# tester.net
KiCad netlist of a schematic drawn in EAGLE
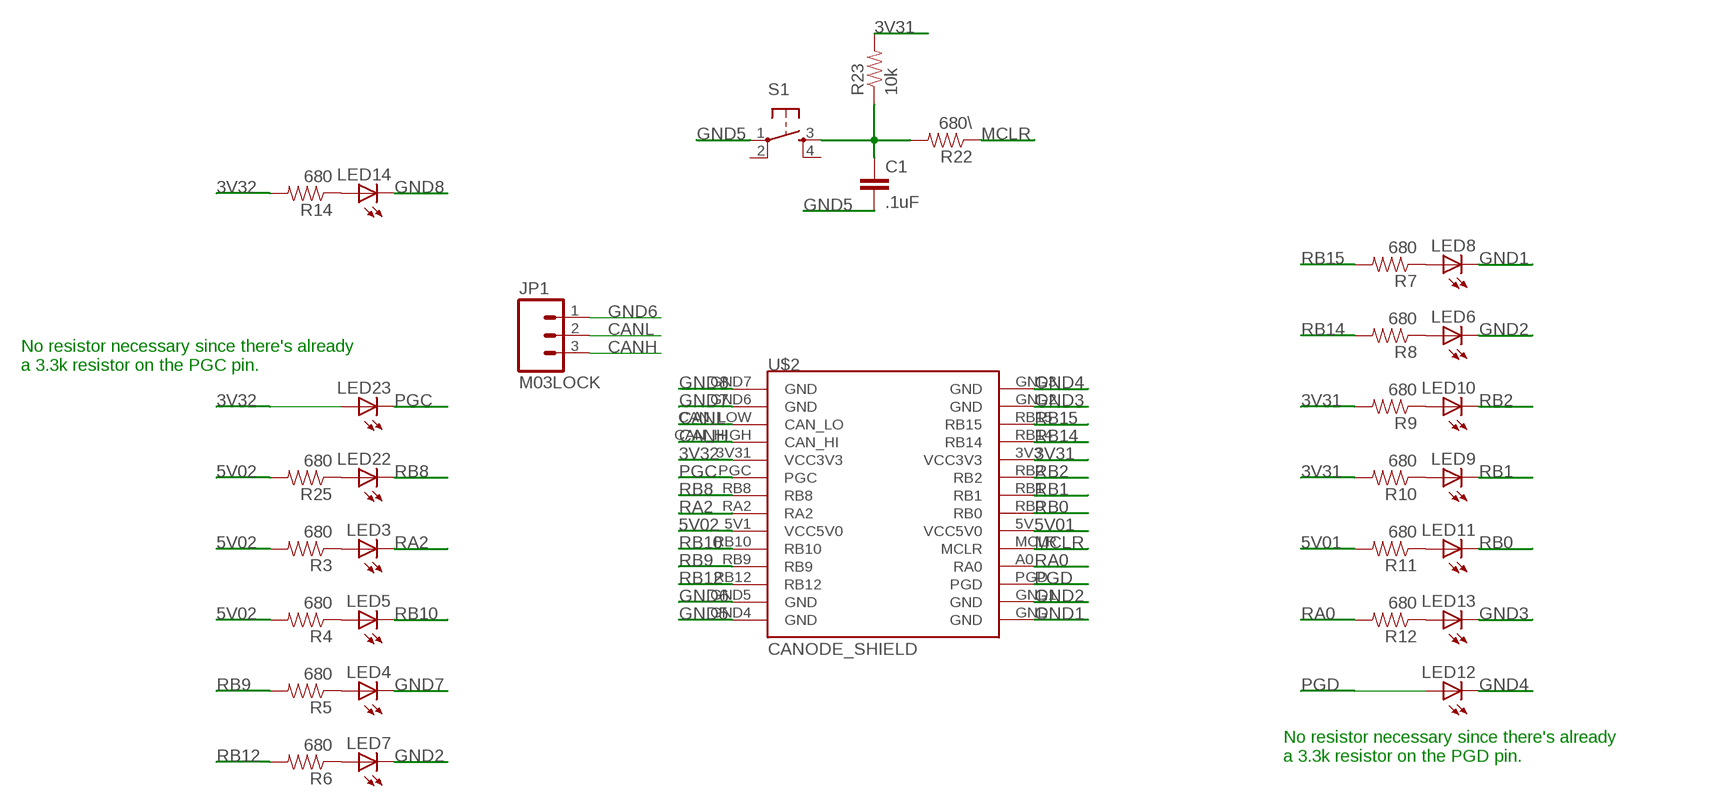
[diagram p0: schematic, sheet 1]

(export (version "E")
  (design (tool "Eeschema 10.0.6"))
  (components
    (comp (ref "C1")
      (value ".1uF")
      (footprint "eagle-import:1206")
      (libsource (lib "eagle-import") (part "CAP1206"))
    )
    (comp (ref "JP1")
      (value "M03LOCK")
      (footprint "eagle-import:1X03_LOCK")
      (libsource (lib "eagle-import") (part "M03LOCK"))
    )
    (comp (ref "LED3")
      (value "LED1206")
      (footprint "eagle-import:LED-1206")
      (libsource (lib "eagle-import") (part "LED1206"))
    )
    (comp (ref "LED4")
      (value "LED1206")
      (footprint "eagle-import:LED-1206")
      (libsource (lib "eagle-import") (part "LED1206"))
    )
    (comp (ref "LED5")
      (value "LED1206")
      (footprint "eagle-import:LED-1206")
      (libsource (lib "eagle-import") (part "LED1206"))
    )
    (comp (ref "LED6")
      (value "LED1206")
      (footprint "eagle-import:LED-1206")
      (libsource (lib "eagle-import") (part "LED1206"))
    )
    (comp (ref "LED7")
      (value "LED1206")
      (footprint "eagle-import:LED-1206")
      (libsource (lib "eagle-import") (part "LED1206"))
    )
    (comp (ref "LED8")
      (value "LED1206")
      (footprint "eagle-import:LED-1206")
      (libsource (lib "eagle-import") (part "LED1206"))
    )
    (comp (ref "LED9")
      (value "LED1206")
      (footprint "eagle-import:LED-1206")
      (libsource (lib "eagle-import") (part "LED1206"))
    )
    (comp (ref "LED10")
      (value "LED1206")
      (footprint "eagle-import:LED-1206")
      (libsource (lib "eagle-import") (part "LED1206"))
    )
    (comp (ref "LED11")
      (value "LED1206")
      (footprint "eagle-import:LED-1206")
      (libsource (lib "eagle-import") (part "LED1206"))
    )
    (comp (ref "LED12")
      (value "LED1206")
      (footprint "eagle-import:LED-1206")
      (libsource (lib "eagle-import") (part "LED1206"))
    )
    (comp (ref "LED13")
      (value "LED1206")
      (footprint "eagle-import:LED-1206")
      (libsource (lib "eagle-import") (part "LED1206"))
    )
    (comp (ref "LED14")
      (value "LED1206")
      (footprint "eagle-import:LED-1206")
      (libsource (lib "eagle-import") (part "LED1206"))
    )
    (comp (ref "LED22")
      (value "LED1206")
      (footprint "eagle-import:LED-1206")
      (libsource (lib "eagle-import") (part "LED1206"))
    )
    (comp (ref "LED23")
      (value "LED1206")
      (footprint "eagle-import:LED-1206")
      (libsource (lib "eagle-import") (part "LED1206"))
    )
    (comp (ref "R3")
      (value "680")
      (footprint "eagle-import:0805")
      (libsource (lib "eagle-import") (part "RESISTOR0805-RES"))
    )
    (comp (ref "R4")
      (value "680")
      (footprint "eagle-import:0805")
      (libsource (lib "eagle-import") (part "RESISTOR0805-RES"))
    )
    (comp (ref "R5")
      (value "680")
      (footprint "eagle-import:0805")
      (libsource (lib "eagle-import") (part "RESISTOR0805-RES"))
    )
    (comp (ref "R6")
      (value "680")
      (footprint "eagle-import:0805")
      (libsource (lib "eagle-import") (part "RESISTOR0805-RES"))
    )
    (comp (ref "R7")
      (value "680")
      (footprint "eagle-import:0805")
      (libsource (lib "eagle-import") (part "RESISTOR0805-RES"))
    )
    (comp (ref "R8")
      (value "680")
      (footprint "eagle-import:0805")
      (libsource (lib "eagle-import") (part "RESISTOR0805-RES"))
    )
    (comp (ref "R9")
      (value "680")
      (footprint "eagle-import:0805")
      (libsource (lib "eagle-import") (part "RESISTOR0805-RES"))
    )
    (comp (ref "R10")
      (value "680")
      (footprint "eagle-import:0805")
      (libsource (lib "eagle-import") (part "RESISTOR0805-RES"))
    )
    (comp (ref "R11")
      (value "680")
      (footprint "eagle-import:0805")
      (libsource (lib "eagle-import") (part "RESISTOR0805-RES"))
    )
    (comp (ref "R12")
      (value "680")
      (footprint "eagle-import:0805")
      (libsource (lib "eagle-import") (part "RESISTOR0805-RES"))
    )
    (comp (ref "R14")
      (value "680")
      (footprint "eagle-import:0805")
      (libsource (lib "eagle-import") (part "RESISTOR0805-RES"))
    )
    (comp (ref "R22")
      (value "680\\")
      (footprint "eagle-import:0805")
      (libsource (lib "eagle-import") (part "RESISTOR0805-RES"))
    )
    (comp (ref "R23")
      (value "10k")
      (footprint "eagle-import:0805")
      (libsource (lib "eagle-import") (part "RESISTOR0805-RES"))
    )
    (comp (ref "R25")
      (value "680")
      (footprint "eagle-import:0805")
      (libsource (lib "eagle-import") (part "RESISTOR0805-RES"))
    )
    (comp (ref "S1")
      (value "TAC_SWITCHPTH")
      (footprint "eagle-import:B3F-1020")
      (libsource (lib "eagle-import") (part "TAC_SWITCHPTH"))
    )
    (comp (ref "U$2")
      (value "CANODE_SHIELD")
      (footprint "eagle-import:CANODE_SHIELD")
      (libsource (lib "eagle-import") (part "CANODE_SHIELD"))
    )
  )
  (nets
    (net (code "1") (name "/3V31") (class "Default")
      (node (ref "R10") (pin "2") (pinfunction "2_2") (pintype "passive"))
      (node (ref "R23") (pin "2") (pinfunction "2_2") (pintype "passive"))
      (node (ref "R9") (pin "2") (pinfunction "2_2") (pintype "passive"))
      (node (ref "U$2") (pin "3V3") (pinfunction "VCC3V3_3V3") (pintype "bidirectional"))
    )
    (net (code "2") (name "/3V32") (class "Default")
      (node (ref "LED23") (pin "A") (pinfunction "A_A") (pintype "passive"))
      (node (ref "R14") (pin "2") (pinfunction "2_2") (pintype "passive"))
      (node (ref "U$2") (pin "3V31") (pinfunction "VCC3V3_3V31") (pintype "bidirectional"))
    )
    (net (code "3") (name "/5V01") (class "Default")
      (node (ref "R11") (pin "2") (pinfunction "2_2") (pintype "passive"))
      (node (ref "U$2") (pin "5V") (pinfunction "VCC5V0_5V") (pintype "bidirectional"))
    )
    (net (code "4") (name "/5V02") (class "Default")
      (node (ref "R25") (pin "2") (pinfunction "2_2") (pintype "passive"))
      (node (ref "R3") (pin "2") (pinfunction "2_2") (pintype "passive"))
      (node (ref "R4") (pin "2") (pinfunction "2_2") (pintype "passive"))
      (node (ref "U$2") (pin "5V1") (pinfunction "VCC5V0_5V1") (pintype "bidirectional"))
    )
    (net (code "5") (name "/CANH") (class "Default")
      (node (ref "JP1") (pin "3") (pinfunction "3_3") (pintype "passive"))
      (node (ref "U$2") (pin "CAN_HIGH") (pinfunction "CAN_HI_CAN_HIGH") (pintype "bidirectional"))
    )
    (net (code "6") (name "/CANL") (class "Default")
      (node (ref "JP1") (pin "2") (pinfunction "2_2") (pintype "passive"))
      (node (ref "U$2") (pin "CAN_LOW") (pinfunction "CAN_LO_CAN_LOW") (pintype "bidirectional"))
    )
    (net (code "7") (name "/GND1") (class "Default")
      (node (ref "LED8") (pin "C") (pinfunction "C_C") (pintype "passive"))
      (node (ref "U$2") (pin "GND") (pinfunction "GND_GND") (pintype "bidirectional"))
    )
    (net (code "8") (name "/GND2") (class "Default")
      (node (ref "LED6") (pin "C") (pinfunction "C_C") (pintype "passive"))
      (node (ref "LED7") (pin "C") (pinfunction "C_C") (pintype "passive"))
      (node (ref "U$2") (pin "GND1") (pinfunction "GND_GND1") (pintype "bidirectional"))
    )
    (net (code "9") (name "/GND3") (class "Default")
      (node (ref "LED13") (pin "C") (pinfunction "C_C") (pintype "passive"))
      (node (ref "U$2") (pin "GND2") (pinfunction "GND_GND2") (pintype "bidirectional"))
    )
    (net (code "10") (name "/GND4") (class "Default")
      (node (ref "LED12") (pin "C") (pinfunction "C_C") (pintype "passive"))
      (node (ref "U$2") (pin "GND3") (pinfunction "GND_GND3") (pintype "bidirectional"))
    )
    (net (code "11") (name "/GND5") (class "Default")
      (node (ref "C1") (pin "2") (pinfunction "2_2") (pintype "passive"))
      (node (ref "S1") (pin "1") (pinfunction "1_1") (pintype "passive"))
      (node (ref "U$2") (pin "GND4") (pinfunction "GND_GND4") (pintype "bidirectional"))
    )
    (net (code "12") (name "/GND6") (class "Default")
      (node (ref "JP1") (pin "1") (pinfunction "1_1") (pintype "passive"))
      (node (ref "U$2") (pin "GND5") (pinfunction "GND_GND5") (pintype "bidirectional"))
    )
    (net (code "13") (name "/GND7") (class "Default")
      (node (ref "LED4") (pin "C") (pinfunction "C_C") (pintype "passive"))
      (node (ref "U$2") (pin "GND6") (pinfunction "GND_GND6") (pintype "bidirectional"))
    )
    (net (code "14") (name "/GND8") (class "Default")
      (node (ref "LED14") (pin "C") (pinfunction "C_C") (pintype "passive"))
      (node (ref "U$2") (pin "GND7") (pinfunction "GND_GND7") (pintype "bidirectional"))
    )
    (net (code "15") (name "/MCLR") (class "Default")
      (node (ref "R22") (pin "1") (pinfunction "1_1") (pintype "passive"))
      (node (ref "U$2") (pin "MCLR") (pinfunction "MCLR_MCLR") (pintype "bidirectional"))
    )
    (net (code "16") (name "/PGC") (class "Default")
      (node (ref "LED23") (pin "C") (pinfunction "C_C") (pintype "passive"))
      (node (ref "U$2") (pin "PGC") (pinfunction "PGC_PGC") (pintype "bidirectional"))
    )
    (net (code "17") (name "/PGD") (class "Default")
      (node (ref "LED12") (pin "A") (pinfunction "A_A") (pintype "passive"))
      (node (ref "U$2") (pin "PGD") (pinfunction "PGD_PGD") (pintype "bidirectional"))
    )
    (net (code "18") (name "/RA0") (class "Default")
      (node (ref "R12") (pin "2") (pinfunction "2_2") (pintype "passive"))
      (node (ref "U$2") (pin "A0") (pinfunction "RA0_A0") (pintype "bidirectional"))
    )
    (net (code "19") (name "/RA2") (class "Default")
      (node (ref "LED3") (pin "C") (pinfunction "C_C") (pintype "passive"))
      (node (ref "U$2") (pin "RA2") (pinfunction "RA2_RA2") (pintype "bidirectional"))
    )
    (net (code "20") (name "/RB0") (class "Default")
      (node (ref "LED11") (pin "C") (pinfunction "C_C") (pintype "passive"))
      (node (ref "U$2") (pin "RB0") (pinfunction "RB0_RB0") (pintype "bidirectional"))
    )
    (net (code "21") (name "/RB1") (class "Default")
      (node (ref "LED9") (pin "C") (pinfunction "C_C") (pintype "passive"))
      (node (ref "U$2") (pin "RB1") (pinfunction "RB1_RB1") (pintype "bidirectional"))
    )
    (net (code "22") (name "/RB2") (class "Default")
      (node (ref "LED10") (pin "C") (pinfunction "C_C") (pintype "passive"))
      (node (ref "U$2") (pin "RB2") (pinfunction "RB2_RB2") (pintype "bidirectional"))
    )
    (net (code "23") (name "/RB8") (class "Default")
      (node (ref "LED22") (pin "C") (pinfunction "C_C") (pintype "passive"))
      (node (ref "U$2") (pin "RB8") (pinfunction "RB8_RB8") (pintype "bidirectional"))
    )
    (net (code "24") (name "/RB9") (class "Default")
      (node (ref "R5") (pin "2") (pinfunction "2_2") (pintype "passive"))
      (node (ref "U$2") (pin "RB9") (pinfunction "RB9_RB9") (pintype "bidirectional"))
    )
    (net (code "25") (name "/RB10") (class "Default")
      (node (ref "LED5") (pin "C") (pinfunction "C_C") (pintype "passive"))
      (node (ref "U$2") (pin "RB10") (pinfunction "RB10_RB10") (pintype "bidirectional"))
    )
    (net (code "26") (name "/RB12") (class "Default")
      (node (ref "R6") (pin "2") (pinfunction "2_2") (pintype "passive"))
      (node (ref "U$2") (pin "RB12") (pinfunction "RB12_RB12") (pintype "bidirectional"))
    )
    (net (code "27") (name "/RB14") (class "Default")
      (node (ref "R8") (pin "2") (pinfunction "2_2") (pintype "passive"))
      (node (ref "U$2") (pin "RB14") (pinfunction "RB14_RB14") (pintype "bidirectional"))
    )
    (net (code "28") (name "/RB15") (class "Default")
      (node (ref "R7") (pin "2") (pinfunction "2_2") (pintype "passive"))
      (node (ref "U$2") (pin "RB15") (pinfunction "RB15_RB15") (pintype "bidirectional"))
    )
    (net (code "29") (name "Net-(C1-Pad1)") (class "Default")
      (node (ref "C1") (pin "1") (pinfunction "1_1") (pintype "passive"))
      (node (ref "R22") (pin "2") (pinfunction "2_2") (pintype "passive"))
      (node (ref "R23") (pin "1") (pinfunction "1_1") (pintype "passive"))
      (node (ref "S1") (pin "3") (pinfunction "3_3") (pintype "passive"))
    )
    (net (code "30") (name "Net-(LED3-PadA)") (class "Default")
      (node (ref "LED3") (pin "A") (pinfunction "A_A") (pintype "passive"))
      (node (ref "R3") (pin "1") (pinfunction "1_1") (pintype "passive"))
    )
    (net (code "31") (name "Net-(LED4-PadA)") (class "Default")
      (node (ref "LED4") (pin "A") (pinfunction "A_A") (pintype "passive"))
      (node (ref "R5") (pin "1") (pinfunction "1_1") (pintype "passive"))
    )
    (net (code "32") (name "Net-(LED5-PadA)") (class "Default")
      (node (ref "LED5") (pin "A") (pinfunction "A_A") (pintype "passive"))
      (node (ref "R4") (pin "1") (pinfunction "1_1") (pintype "passive"))
    )
    (net (code "33") (name "Net-(LED6-PadA)") (class "Default")
      (node (ref "LED6") (pin "A") (pinfunction "A_A") (pintype "passive"))
      (node (ref "R8") (pin "1") (pinfunction "1_1") (pintype "passive"))
    )
    (net (code "34") (name "Net-(LED7-PadA)") (class "Default")
      (node (ref "LED7") (pin "A") (pinfunction "A_A") (pintype "passive"))
      (node (ref "R6") (pin "1") (pinfunction "1_1") (pintype "passive"))
    )
    (net (code "35") (name "Net-(LED8-PadA)") (class "Default")
      (node (ref "LED8") (pin "A") (pinfunction "A_A") (pintype "passive"))
      (node (ref "R7") (pin "1") (pinfunction "1_1") (pintype "passive"))
    )
    (net (code "36") (name "Net-(LED9-PadA)") (class "Default")
      (node (ref "LED9") (pin "A") (pinfunction "A_A") (pintype "passive"))
      (node (ref "R10") (pin "1") (pinfunction "1_1") (pintype "passive"))
    )
    (net (code "37") (name "Net-(LED10-PadA)") (class "Default")
      (node (ref "LED10") (pin "A") (pinfunction "A_A") (pintype "passive"))
      (node (ref "R9") (pin "1") (pinfunction "1_1") (pintype "passive"))
    )
    (net (code "38") (name "Net-(LED11-PadA)") (class "Default")
      (node (ref "LED11") (pin "A") (pinfunction "A_A") (pintype "passive"))
      (node (ref "R11") (pin "1") (pinfunction "1_1") (pintype "passive"))
    )
    (net (code "39") (name "Net-(LED13-PadA)") (class "Default")
      (node (ref "LED13") (pin "A") (pinfunction "A_A") (pintype "passive"))
      (node (ref "R12") (pin "1") (pinfunction "1_1") (pintype "passive"))
    )
    (net (code "40") (name "Net-(LED14-PadA)") (class "Default")
      (node (ref "LED14") (pin "A") (pinfunction "A_A") (pintype "passive"))
      (node (ref "R14") (pin "1") (pinfunction "1_1") (pintype "passive"))
    )
    (net (code "41") (name "Net-(LED22-PadA)") (class "Default")
      (node (ref "LED22") (pin "A") (pinfunction "A_A") (pintype "passive"))
      (node (ref "R25") (pin "1") (pinfunction "1_1") (pintype "passive"))
    )
    (net (code "42") (name "unconnected-(S1-Pad2)") (class "Default")
      (node (ref "S1") (pin "2") (pinfunction "2_2") (pintype "passive"))
    )
    (net (code "43") (name "unconnected-(S1-Pad4)") (class "Default")
      (node (ref "S1") (pin "4") (pinfunction "4_4") (pintype "passive"))
    )
  )
)
